# FPC_ADAPTOR.net
KiCad netlist of a schematic drawn in Altium Designer
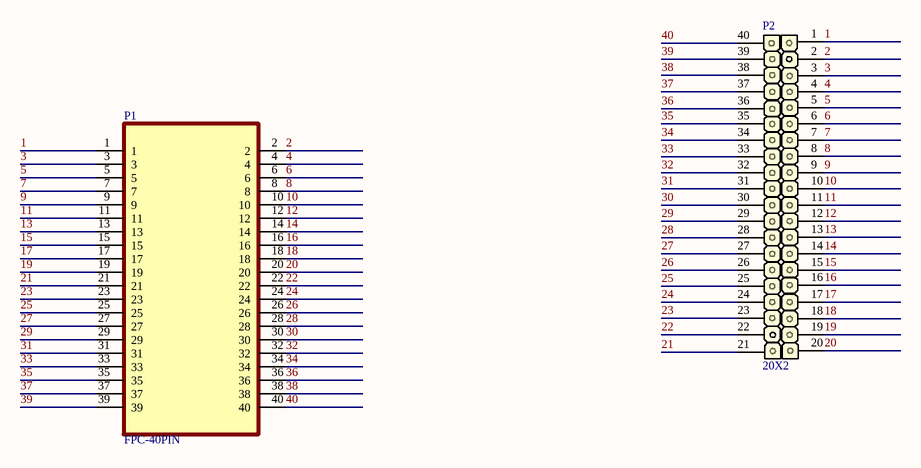
[diagram p0: FPC_ADAPTOR.SchDoc]

(export (version "E")
  (design (tool "Eeschema 10.0.6"))
  (components
    (comp (ref "P1")
      (value "FPC-40PIN")
      (footprint "FPC-40PIN-0.5MM")
      (libsource (lib "LuhmannConnectörsLıbrary") (part "FPC-40PIN"))
    )
    (comp (ref "P2")
      (value "20X2")
      (footprint "2X20_FPC")
      (libsource (lib "LuhmannConnectörsLıbrary") (part "20X2"))
    )
  )
  (nets
    (net (code "1") (name "/1") (class "Default")
      (node (ref "P1") (pin "1") (pinfunction "1_1") (pintype "passive"))
      (node (ref "P2") (pin "1") (pintype "passive"))
    )
    (net (code "2") (name "/2") (class "Default")
      (node (ref "P1") (pin "2") (pinfunction "2_2") (pintype "passive"))
      (node (ref "P2") (pin "2") (pintype "passive"))
    )
    (net (code "3") (name "/3") (class "Default")
      (node (ref "P1") (pin "3") (pinfunction "3_3") (pintype "passive"))
      (node (ref "P2") (pin "3") (pintype "passive"))
    )
    (net (code "4") (name "/4") (class "Default")
      (node (ref "P1") (pin "4") (pinfunction "4_4") (pintype "passive"))
      (node (ref "P2") (pin "4") (pintype "passive"))
    )
    (net (code "5") (name "/5") (class "Default")
      (node (ref "P1") (pin "5") (pinfunction "5_5") (pintype "passive"))
      (node (ref "P2") (pin "5") (pintype "passive"))
    )
    (net (code "6") (name "/6") (class "Default")
      (node (ref "P1") (pin "6") (pinfunction "6_6") (pintype "passive"))
      (node (ref "P2") (pin "6") (pintype "passive"))
    )
    (net (code "7") (name "/7") (class "Default")
      (node (ref "P1") (pin "7") (pinfunction "7_7") (pintype "passive"))
      (node (ref "P2") (pin "7") (pintype "passive"))
    )
    (net (code "8") (name "/8") (class "Default")
      (node (ref "P1") (pin "8") (pinfunction "8_8") (pintype "passive"))
      (node (ref "P2") (pin "8") (pintype "passive"))
    )
    (net (code "9") (name "/9") (class "Default")
      (node (ref "P1") (pin "9") (pinfunction "9_9") (pintype "passive"))
      (node (ref "P2") (pin "9") (pintype "passive"))
    )
    (net (code "10") (name "/10") (class "Default")
      (node (ref "P1") (pin "10") (pinfunction "10_10") (pintype "passive"))
      (node (ref "P2") (pin "10") (pintype "passive"))
    )
    (net (code "11") (name "/11") (class "Default")
      (node (ref "P1") (pin "11") (pinfunction "11_11") (pintype "passive"))
      (node (ref "P2") (pin "11") (pintype "passive"))
    )
    (net (code "12") (name "/12") (class "Default")
      (node (ref "P1") (pin "12") (pinfunction "12_12") (pintype "passive"))
      (node (ref "P2") (pin "12") (pintype "passive"))
    )
    (net (code "13") (name "/13") (class "Default")
      (node (ref "P1") (pin "13") (pinfunction "13_13") (pintype "passive"))
      (node (ref "P2") (pin "13") (pintype "passive"))
    )
    (net (code "14") (name "/14") (class "Default")
      (node (ref "P1") (pin "14") (pinfunction "14_14") (pintype "passive"))
      (node (ref "P2") (pin "14") (pintype "passive"))
    )
    (net (code "15") (name "/15") (class "Default")
      (node (ref "P1") (pin "15") (pinfunction "15_15") (pintype "passive"))
      (node (ref "P2") (pin "15") (pintype "passive"))
    )
    (net (code "16") (name "/16") (class "Default")
      (node (ref "P1") (pin "16") (pinfunction "16_16") (pintype "passive"))
      (node (ref "P2") (pin "16") (pintype "passive"))
    )
    (net (code "17") (name "/17") (class "Default")
      (node (ref "P1") (pin "17") (pinfunction "17_17") (pintype "passive"))
      (node (ref "P2") (pin "17") (pintype "passive"))
    )
    (net (code "18") (name "/18") (class "Default")
      (node (ref "P1") (pin "18") (pinfunction "18_18") (pintype "passive"))
      (node (ref "P2") (pin "18") (pintype "passive"))
    )
    (net (code "19") (name "/19") (class "Default")
      (node (ref "P1") (pin "19") (pinfunction "19_19") (pintype "passive"))
      (node (ref "P2") (pin "19") (pintype "passive"))
    )
    (net (code "20") (name "/20") (class "Default")
      (node (ref "P1") (pin "20") (pinfunction "20_20") (pintype "passive"))
      (node (ref "P2") (pin "20") (pintype "passive"))
    )
    (net (code "21") (name "/21") (class "Default")
      (node (ref "P1") (pin "21") (pinfunction "21_21") (pintype "passive"))
      (node (ref "P2") (pin "21") (pintype "passive"))
    )
    (net (code "22") (name "/22") (class "Default")
      (node (ref "P1") (pin "22") (pinfunction "22_22") (pintype "passive"))
      (node (ref "P2") (pin "22") (pintype "passive"))
    )
    (net (code "23") (name "/23") (class "Default")
      (node (ref "P1") (pin "23") (pinfunction "23_23") (pintype "passive"))
      (node (ref "P2") (pin "23") (pintype "passive"))
    )
    (net (code "24") (name "/24") (class "Default")
      (node (ref "P1") (pin "24") (pinfunction "24_24") (pintype "passive"))
      (node (ref "P2") (pin "24") (pintype "passive"))
    )
    (net (code "25") (name "/25") (class "Default")
      (node (ref "P1") (pin "25") (pinfunction "25_25") (pintype "passive"))
      (node (ref "P2") (pin "25") (pintype "passive"))
    )
    (net (code "26") (name "/26") (class "Default")
      (node (ref "P1") (pin "26") (pinfunction "26_26") (pintype "passive"))
      (node (ref "P2") (pin "26") (pintype "passive"))
    )
    (net (code "27") (name "/27") (class "Default")
      (node (ref "P1") (pin "27") (pinfunction "27_27") (pintype "passive"))
      (node (ref "P2") (pin "27") (pintype "passive"))
    )
    (net (code "28") (name "/28") (class "Default")
      (node (ref "P1") (pin "28") (pinfunction "28_28") (pintype "passive"))
      (node (ref "P2") (pin "28") (pintype "passive"))
    )
    (net (code "29") (name "/29") (class "Default")
      (node (ref "P1") (pin "29") (pinfunction "29_29") (pintype "passive"))
      (node (ref "P2") (pin "29") (pintype "passive"))
    )
    (net (code "30") (name "/30") (class "Default")
      (node (ref "P1") (pin "30") (pinfunction "30_30") (pintype "passive"))
      (node (ref "P2") (pin "30") (pintype "passive"))
    )
    (net (code "31") (name "/31") (class "Default")
      (node (ref "P1") (pin "31") (pinfunction "31_31") (pintype "passive"))
      (node (ref "P2") (pin "31") (pintype "passive"))
    )
    (net (code "32") (name "/32") (class "Default")
      (node (ref "P1") (pin "32") (pinfunction "32_32") (pintype "passive"))
      (node (ref "P2") (pin "32") (pintype "passive"))
    )
    (net (code "33") (name "/33") (class "Default")
      (node (ref "P1") (pin "33") (pinfunction "33_33") (pintype "passive"))
      (node (ref "P2") (pin "33") (pintype "passive"))
    )
    (net (code "34") (name "/34") (class "Default")
      (node (ref "P1") (pin "34") (pinfunction "34_34") (pintype "passive"))
      (node (ref "P2") (pin "34") (pintype "passive"))
    )
    (net (code "35") (name "/35") (class "Default")
      (node (ref "P1") (pin "35") (pinfunction "35_35") (pintype "passive"))
      (node (ref "P2") (pin "35") (pintype "passive"))
    )
    (net (code "36") (name "/36") (class "Default")
      (node (ref "P1") (pin "36") (pinfunction "36_36") (pintype "passive"))
      (node (ref "P2") (pin "36") (pintype "passive"))
    )
    (net (code "37") (name "/37") (class "Default")
      (node (ref "P1") (pin "37") (pinfunction "37_37") (pintype "passive"))
      (node (ref "P2") (pin "37") (pintype "passive"))
    )
    (net (code "38") (name "/38") (class "Default")
      (node (ref "P1") (pin "38") (pinfunction "38_38") (pintype "passive"))
      (node (ref "P2") (pin "38") (pintype "passive"))
    )
    (net (code "39") (name "/39") (class "Default")
      (node (ref "P1") (pin "39") (pinfunction "39_39") (pintype "passive"))
      (node (ref "P2") (pin "39") (pintype "passive"))
    )
    (net (code "40") (name "/40") (class "Default")
      (node (ref "P1") (pin "40") (pinfunction "40_40") (pintype "passive"))
      (node (ref "P2") (pin "40") (pintype "passive"))
    )
  )
)
